# Vl822.net
KiCad netlist of a schematic drawn in Altium Designer
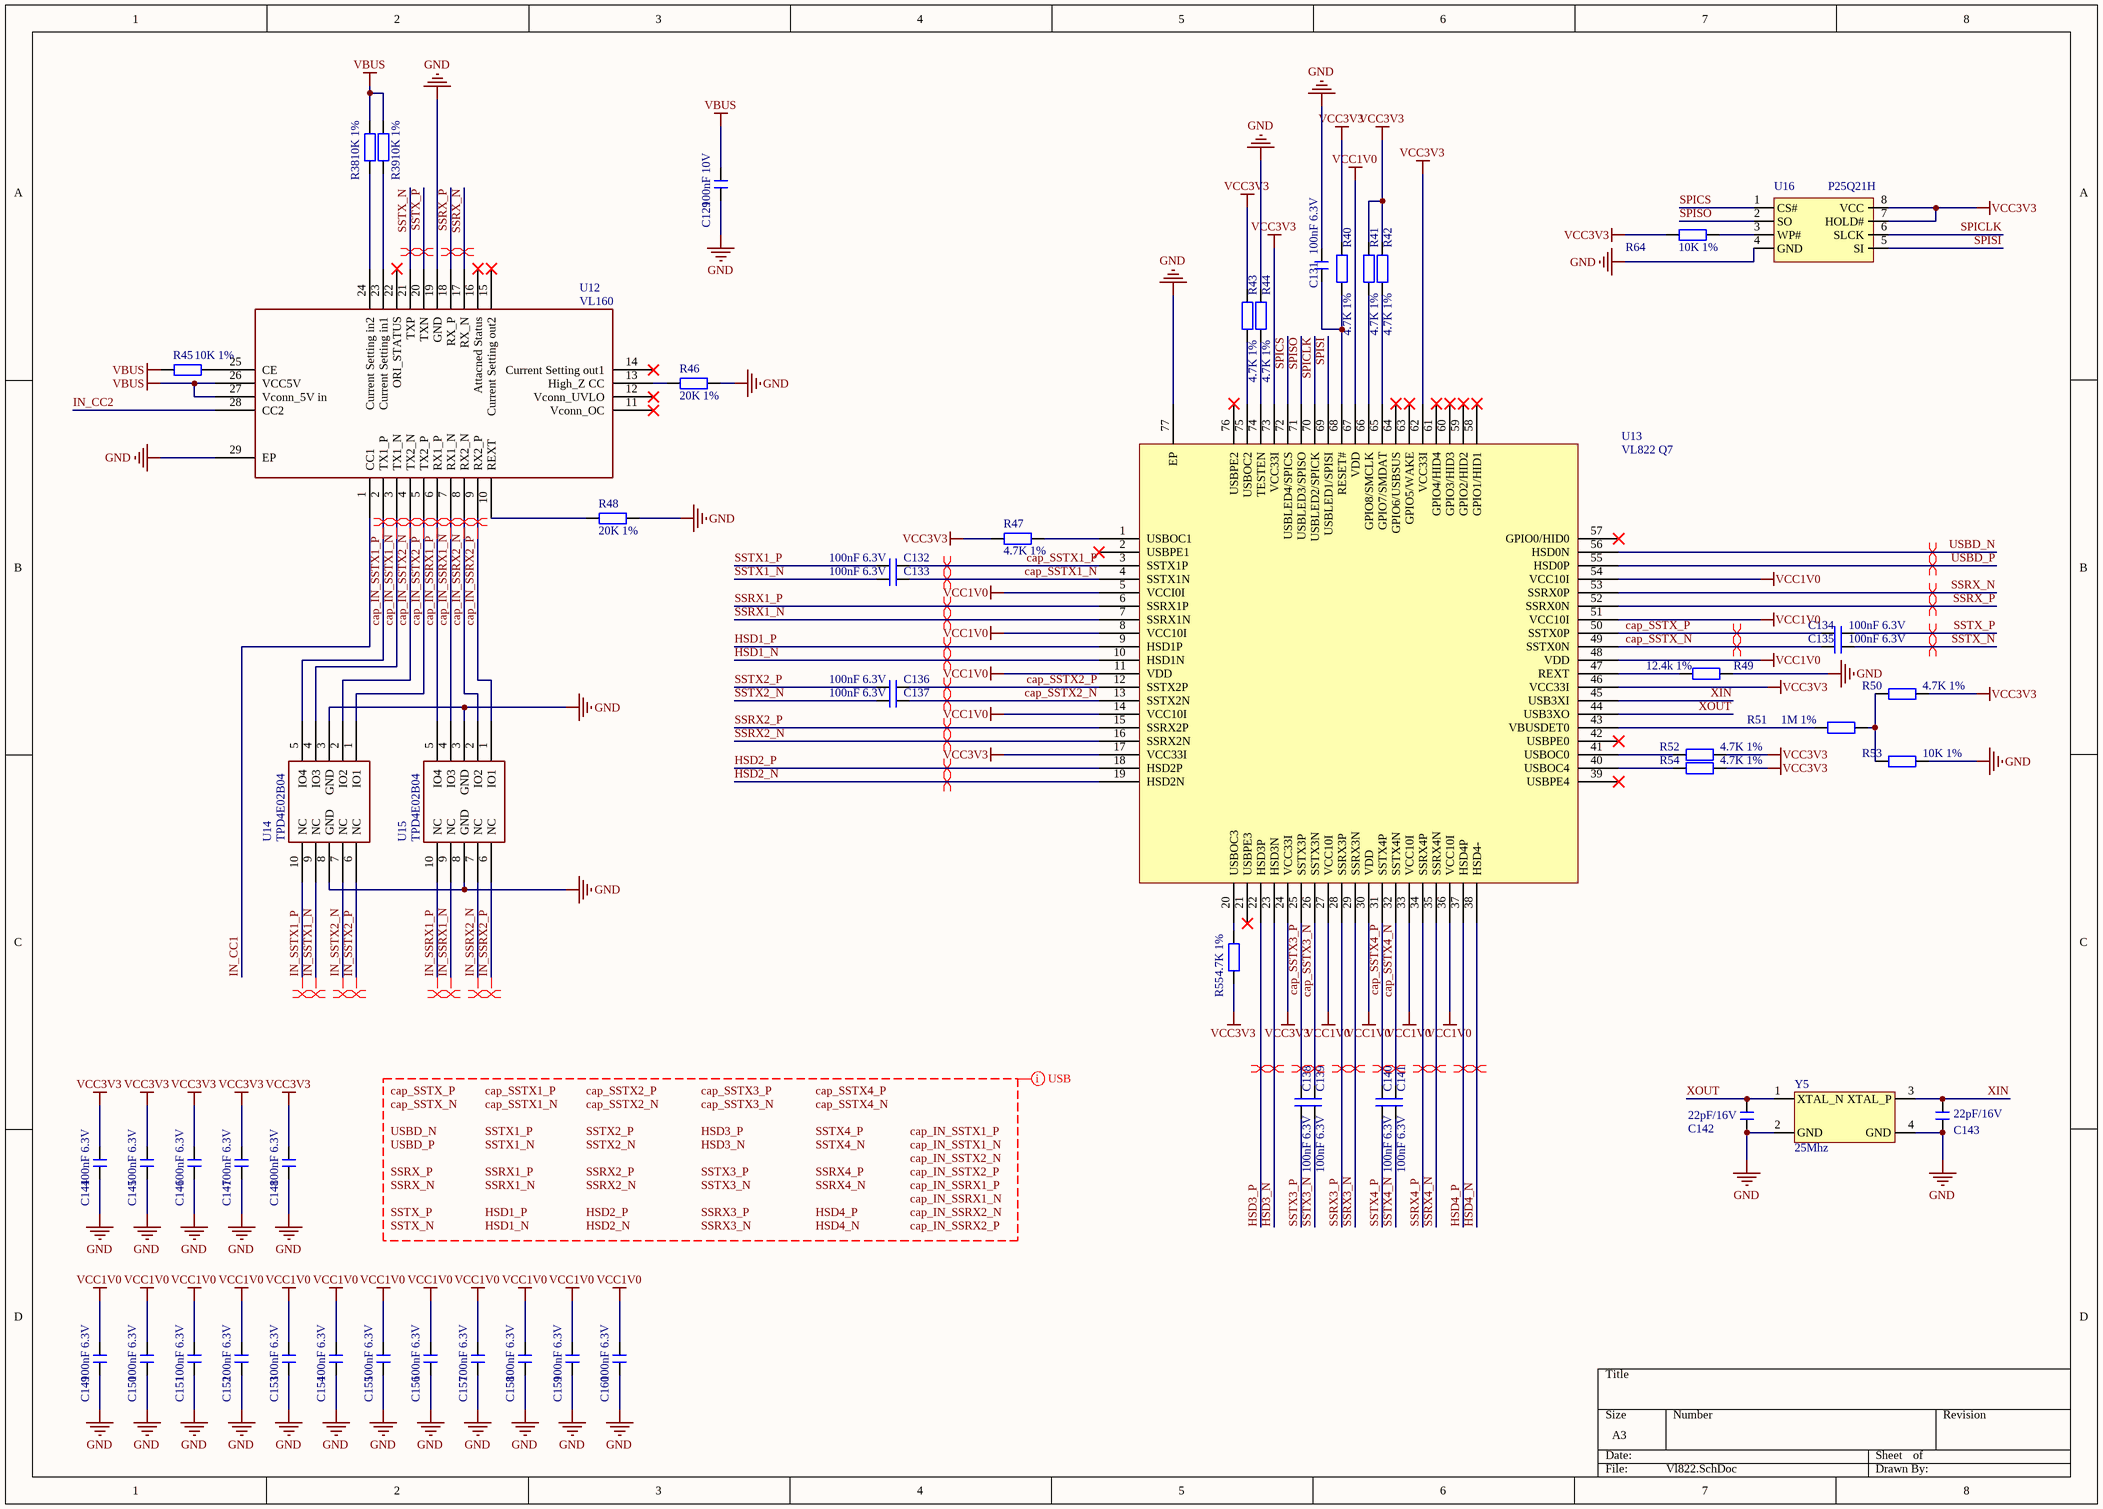
[diagram p0: Vl822.SchDoc]

(export (version "E")
  (design (tool "Eeschema 10.0.6"))
  (components
    (comp (ref "C129")
      (value "100nF 10V")
      (footprint "C0402_L")
      (description "无极性贴片电容")
      (fields (field (name "版权归属") "源创客"))
      (libsource (lib "Capacitor") (part "C"))
    )
    (comp (ref "C131")
      (value "100nF 6.3V")
      (footprint "C0402_L")
      (description "无极性贴片电容")
      (fields (field (name "版权归属") "源创客"))
      (libsource (lib "Capacitor") (part "C"))
    )
    (comp (ref "C132")
      (value "100nF 6.3V")
      (footprint "C0402_L")
      (description "无极性贴片电容")
      (fields (field (name "版权归属") "源创客"))
      (libsource (lib "Capacitor") (part "C"))
    )
    (comp (ref "C133")
      (value "100nF 6.3V")
      (footprint "C0402_L")
      (description "无极性贴片电容")
      (fields (field (name "版权归属") "源创客"))
      (libsource (lib "Capacitor") (part "C"))
    )
    (comp (ref "C134")
      (value "100nF 6.3V")
      (footprint "C0402_L")
      (description "无极性贴片电容")
      (fields (field (name "版权归属") "源创客"))
      (libsource (lib "Capacitor") (part "C"))
    )
    (comp (ref "C135")
      (value "100nF 6.3V")
      (footprint "C0402_L")
      (description "无极性贴片电容")
      (fields (field (name "版权归属") "源创客"))
      (libsource (lib "Capacitor") (part "C"))
    )
    (comp (ref "C136")
      (value "100nF 6.3V")
      (footprint "C0402_L")
      (description "无极性贴片电容")
      (fields (field (name "版权归属") "源创客"))
      (libsource (lib "Capacitor") (part "C"))
    )
    (comp (ref "C137")
      (value "100nF 6.3V")
      (footprint "C0402_L")
      (description "无极性贴片电容")
      (fields (field (name "版权归属") "源创客"))
      (libsource (lib "Capacitor") (part "C"))
    )
    (comp (ref "C138")
      (value "100nF 6.3V")
      (footprint "C0402_L")
      (description "无极性贴片电容")
      (fields (field (name "版权归属") "源创客"))
      (libsource (lib "Capacitor") (part "C"))
    )
    (comp (ref "C139")
      (value "100nF 6.3V")
      (footprint "C0402_L")
      (description "无极性贴片电容")
      (fields (field (name "版权归属") "源创客"))
      (libsource (lib "Capacitor") (part "C"))
    )
    (comp (ref "C140")
      (value "100nF 6.3V")
      (footprint "C0402_L")
      (description "无极性贴片电容")
      (fields (field (name "版权归属") "源创客"))
      (libsource (lib "Capacitor") (part "C"))
    )
    (comp (ref "C141")
      (value "100nF 6.3V")
      (footprint "C0402_L")
      (description "无极性贴片电容")
      (fields (field (name "版权归属") "源创客"))
      (libsource (lib "Capacitor") (part "C"))
    )
    (comp (ref "C142")
      (value "22pF/16V")
      (footprint "C0402_L")
      (description "无极性贴片电容")
      (fields (field (name "版权归属") "源创客"))
      (libsource (lib "Capacitor") (part "C"))
    )
    (comp (ref "C143")
      (value "22pF/16V")
      (footprint "C0402_L")
      (description "无极性贴片电容")
      (fields (field (name "版权归属") "源创客"))
      (libsource (lib "Capacitor") (part "C"))
    )
    (comp (ref "C144")
      (value "100nF 6.3V")
      (footprint "C0402_L")
      (description "无极性贴片电容")
      (fields (field (name "版权归属") "源创客"))
      (libsource (lib "Capacitor") (part "C"))
    )
    (comp (ref "C145")
      (value "100nF 6.3V")
      (footprint "C0402_L")
      (description "无极性贴片电容")
      (fields (field (name "版权归属") "源创客"))
      (libsource (lib "Capacitor") (part "C"))
    )
    (comp (ref "C146")
      (value "100nF 6.3V")
      (footprint "C0402_L")
      (description "无极性贴片电容")
      (fields (field (name "版权归属") "源创客"))
      (libsource (lib "Capacitor") (part "C"))
    )
    (comp (ref "C147")
      (value "100nF 6.3V")
      (footprint "C0402_L")
      (description "无极性贴片电容")
      (fields (field (name "版权归属") "源创客"))
      (libsource (lib "Capacitor") (part "C"))
    )
    (comp (ref "C148")
      (value "100nF 6.3V")
      (footprint "C0402_L")
      (description "无极性贴片电容")
      (fields (field (name "版权归属") "源创客"))
      (libsource (lib "Capacitor") (part "C"))
    )
    (comp (ref "C149")
      (value "100nF 6.3V")
      (footprint "C0402_L")
      (description "无极性贴片电容")
      (fields (field (name "版权归属") "源创客"))
      (libsource (lib "Capacitor") (part "C"))
    )
    (comp (ref "C150")
      (value "100nF 6.3V")
      (footprint "C0402_L")
      (description "无极性贴片电容")
      (fields (field (name "版权归属") "源创客"))
      (libsource (lib "Capacitor") (part "C"))
    )
    (comp (ref "C151")
      (value "100nF 6.3V")
      (footprint "C0402_L")
      (description "无极性贴片电容")
      (fields (field (name "版权归属") "源创客"))
      (libsource (lib "Capacitor") (part "C"))
    )
    (comp (ref "C152")
      (value "100nF 6.3V")
      (footprint "C0402_L")
      (description "无极性贴片电容")
      (fields (field (name "版权归属") "源创客"))
      (libsource (lib "Capacitor") (part "C"))
    )
    (comp (ref "C153")
      (value "100nF 6.3V")
      (footprint "C0402_L")
      (description "无极性贴片电容")
      (fields (field (name "版权归属") "源创客"))
      (libsource (lib "Capacitor") (part "C"))
    )
    (comp (ref "C154")
      (value "100nF 6.3V")
      (footprint "C0402_L")
      (description "无极性贴片电容")
      (fields (field (name "版权归属") "源创客"))
      (libsource (lib "Capacitor") (part "C"))
    )
    (comp (ref "C155")
      (value "100nF 6.3V")
      (footprint "C0402_L")
      (description "无极性贴片电容")
      (fields (field (name "版权归属") "源创客"))
      (libsource (lib "Capacitor") (part "C"))
    )
    (comp (ref "C156")
      (value "100nF 6.3V")
      (footprint "C0402_L")
      (description "无极性贴片电容")
      (fields (field (name "版权归属") "源创客"))
      (libsource (lib "Capacitor") (part "C"))
    )
    (comp (ref "C157")
      (value "100nF 6.3V")
      (footprint "C0402_L")
      (description "无极性贴片电容")
      (fields (field (name "版权归属") "源创客"))
      (libsource (lib "Capacitor") (part "C"))
    )
    (comp (ref "C158")
      (value "100nF 6.3V")
      (footprint "C0402_L")
      (description "无极性贴片电容")
      (fields (field (name "版权归属") "源创客"))
      (libsource (lib "Capacitor") (part "C"))
    )
    (comp (ref "C159")
      (value "100nF 6.3V")
      (footprint "C0402_L")
      (description "无极性贴片电容")
      (fields (field (name "版权归属") "源创客"))
      (libsource (lib "Capacitor") (part "C"))
    )
    (comp (ref "C160")
      (value "100nF 6.3V")
      (footprint "C0402_L")
      (description "无极性贴片电容")
      (fields (field (name "版权归属") "源创客"))
      (libsource (lib "Capacitor") (part "C"))
    )
    (comp (ref "R38")
      (value "10K 1%")
      (footprint "R0402_L")
      (description "贴片电阻")
      (fields (field (name "版权归属") "源创客"))
      (libsource (lib "Resistor") (part "R"))
    )
    (comp (ref "R39")
      (value "10K 1%")
      (footprint "R0402_L")
      (description "贴片电阻")
      (fields (field (name "版权归属") "源创客"))
      (libsource (lib "Resistor") (part "R"))
    )
    (comp (ref "R40")
      (value "4.7K 1%")
      (footprint "R0402_L")
      (description "贴片电阻")
      (fields (field (name "版权归属") "源创客"))
      (libsource (lib "Resistor") (part "R"))
    )
    (comp (ref "R41")
      (value "4.7K 1%")
      (footprint "R0402_L")
      (description "贴片电阻")
      (fields (field (name "版权归属") "源创客"))
      (libsource (lib "Resistor") (part "R"))
    )
    (comp (ref "R42")
      (value "4.7K 1%")
      (footprint "R0402_L")
      (description "贴片电阻")
      (fields (field (name "版权归属") "源创客"))
      (libsource (lib "Resistor") (part "R"))
    )
    (comp (ref "R43")
      (value "4.7K 1%")
      (footprint "R0402_L")
      (description "贴片电阻")
      (fields (field (name "版权归属") "源创客"))
      (libsource (lib "Resistor") (part "R"))
    )
    (comp (ref "R44")
      (value "4.7K 1%")
      (footprint "R0402_L")
      (description "贴片电阻")
      (fields (field (name "版权归属") "源创客"))
      (libsource (lib "Resistor") (part "R"))
    )
    (comp (ref "R45")
      (value "10K 1%")
      (footprint "R0402_L")
      (description "贴片电阻")
      (fields (field (name "版权归属") "源创客"))
      (libsource (lib "Resistor") (part "R"))
    )
    (comp (ref "R46")
      (value "20K 1%")
      (footprint "R0402_L")
      (description "贴片电阻")
      (fields (field (name "版权归属") "源创客"))
      (libsource (lib "Resistor") (part "R"))
    )
    (comp (ref "R47")
      (value "4.7K 1%")
      (footprint "R0402_L")
      (description "贴片电阻")
      (fields (field (name "版权归属") "源创客"))
      (libsource (lib "Resistor") (part "R"))
    )
    (comp (ref "R48")
      (value "20K 1%")
      (footprint "R0402_L")
      (description "贴片电阻")
      (fields (field (name "版权归属") "源创客"))
      (libsource (lib "Resistor") (part "R"))
    )
    (comp (ref "R49")
      (value "12.4k 1%")
      (footprint "R0402_L")
      (description "贴片电阻")
      (fields (field (name "版权归属") "源创客"))
      (libsource (lib "Resistor") (part "R"))
    )
    (comp (ref "R50")
      (value "4.7K 1%")
      (footprint "R0402_L")
      (description "贴片电阻")
      (fields (field (name "版权归属") "源创客"))
      (libsource (lib "Resistor") (part "R"))
    )
    (comp (ref "R51")
      (value "1M 1%")
      (footprint "R0402_L")
      (description "贴片电阻")
      (fields (field (name "版权归属") "源创客"))
      (libsource (lib "Resistor") (part "R"))
    )
    (comp (ref "R52")
      (value "4.7K 1%")
      (footprint "R0402_L")
      (description "贴片电阻")
      (fields (field (name "版权归属") "源创客"))
      (libsource (lib "Resistor") (part "R"))
    )
    (comp (ref "R53")
      (value "10K 1%")
      (footprint "R0402_L")
      (description "贴片电阻")
      (fields (field (name "版权归属") "源创客"))
      (libsource (lib "Resistor") (part "R"))
    )
    (comp (ref "R54")
      (value "4.7K 1%")
      (footprint "R0402_L")
      (description "贴片电阻")
      (fields (field (name "版权归属") "源创客"))
      (libsource (lib "Resistor") (part "R"))
    )
    (comp (ref "R55")
      (value "4.7K 1%")
      (footprint "R0402_L")
      (description "贴片电阻")
      (fields (field (name "版权归属") "源创客"))
      (libsource (lib "Resistor") (part "R"))
    )
    (comp (ref "R64")
      (value "10K 1%")
      (footprint "R0402_L")
      (description "贴片电阻")
      (fields (field (name "版权归属") "源创客"))
      (libsource (lib "Resistor") (part "R"))
    )
    (comp (ref "U12")
      (value "VL160")
      (footprint "MQFN-28_L4.5-W3.5-P0.40-BL-EP")
      (libsource (lib "Brage") (part "VL160"))
    )
    (comp (ref "U13")
      (value "VL822 Q7")
      (footprint "QFN-76_L9.0-W9.0-P0.40-EP6.3-TL")
      (libsource (lib "Brage") (part "VL822 Q7"))
    )
    (comp (ref "U14")
      (value "TPD4E02B04")
      (footprint "DIO_TPD4E02B04DQAR")
      (description "ESD")
      (libsource (lib "Diode") (part "TPD4E02B04"))
    )
    (comp (ref "U15")
      (value "TPD4E02B04")
      (footprint "DIO_TPD4E02B04DQAR")
      (description "ESD")
      (libsource (lib "Diode") (part "TPD4E02B04"))
    )
    (comp (ref "U16") (value "P25Q21H") (footprint "SOP8_L") (libsource (lib "Flash") (part "P25D40H")))
    (comp (ref "Y5") (value "25Mhz") (footprint "OSC 3225-4P") (libsource (lib "Crystal") (part "Crystal")))
  )
  (nets
    (net (code "1") (name "/HSD1_N") (class "Default")
      (node (ref "U13") (pin "10") (pinfunction "HSD1N_10") (pintype "passive"))
    )
    (net (code "2") (name "/HSD1_P") (class "Default")
      (node (ref "U13") (pin "9") (pinfunction "HSD1P_9") (pintype "passive"))
    )
    (net (code "3") (name "/HSD2_N") (class "Default")
      (node (ref "U13") (pin "19") (pinfunction "HSD2N_19") (pintype "passive"))
    )
    (net (code "4") (name "/HSD2_P") (class "Default")
      (node (ref "U13") (pin "18") (pinfunction "HSD2P_18") (pintype "passive"))
    )
    (net (code "5") (name "/HSD3_N") (class "Default")
      (node (ref "U13") (pin "23") (pinfunction "HSD3N_23") (pintype "passive"))
    )
    (net (code "6") (name "/HSD3_P") (class "Default")
      (node (ref "U13") (pin "22") (pinfunction "HSD3P_22") (pintype "passive"))
    )
    (net (code "7") (name "/HSD4_N") (class "Default")
      (node (ref "U13") (pin "38") (pinfunction "HSD4-_38") (pintype "passive"))
    )
    (net (code "8") (name "/HSD4_P") (class "Default")
      (node (ref "U13") (pin "37") (pinfunction "HSD4P_37") (pintype "passive"))
    )
    (net (code "9") (name "/IN_CC1") (class "Default")
      (node (ref "U12") (pin "1") (pinfunction "CC1_1") (pintype "passive"))
    )
    (net (code "10") (name "/IN_CC2") (class "Default")
      (node (ref "U12") (pin "28") (pinfunction "CC2_28") (pintype "passive"))
    )
    (net (code "11") (name "/IN_SSRX1_N") (class "Default")
      (node (ref "U15") (pin "9") (pinfunction "NC_9") (pintype "passive"))
    )
    (net (code "12") (name "/IN_SSRX1_P") (class "Default")
      (node (ref "U15") (pin "10") (pinfunction "NC_10") (pintype "passive"))
    )
    (net (code "13") (name "/IN_SSRX2_N") (class "Default")
      (node (ref "U15") (pin "7") (pinfunction "NC_7") (pintype "passive"))
    )
    (net (code "14") (name "/IN_SSRX2_P") (class "Default")
      (node (ref "U15") (pin "6") (pinfunction "NC_6") (pintype "passive"))
    )
    (net (code "15") (name "/IN_SSTX1_N") (class "Default")
      (node (ref "U14") (pin "9") (pinfunction "NC_9") (pintype "passive"))
    )
    (net (code "16") (name "/IN_SSTX1_P") (class "Default")
      (node (ref "U14") (pin "10") (pinfunction "NC_10") (pintype "passive"))
    )
    (net (code "17") (name "/IN_SSTX2_N") (class "Default")
      (node (ref "U14") (pin "7") (pinfunction "NC_7") (pintype "passive"))
    )
    (net (code "18") (name "/IN_SSTX2_P") (class "Default")
      (node (ref "U14") (pin "6") (pinfunction "NC_6") (pintype "passive"))
    )
    (net (code "19") (name "/SPICLK") (class "Default")
      (node (ref "U13") (pin "70") (pinfunction "USBLED2/SPICK_70") (pintype "passive"))
      (node (ref "U16") (pin "6") (pinfunction "SLCK_6") (pintype "passive"))
    )
    (net (code "20") (name "/SPICS") (class "Default")
      (node (ref "U13") (pin "72") (pinfunction "USBLED4/SPICS_72") (pintype "passive"))
      (node (ref "U16") (pin "1") (pinfunction "CS#_1") (pintype "passive"))
    )
    (net (code "21") (name "/SPISI") (class "Default")
      (node (ref "U13") (pin "69") (pinfunction "USBLED1/SPISI_69") (pintype "passive"))
      (node (ref "U16") (pin "5") (pinfunction "SI_5") (pintype "passive"))
    )
    (net (code "22") (name "/SPISO") (class "Default")
      (node (ref "U13") (pin "71") (pinfunction "USBLED3/SPISO_71") (pintype "passive"))
      (node (ref "U16") (pin "2") (pinfunction "SO_2") (pintype "passive"))
    )
    (net (code "23") (name "/SSRX1_N") (class "Default")
      (node (ref "U13") (pin "7") (pinfunction "SSRX1N_7") (pintype "passive"))
    )
    (net (code "24") (name "/SSRX1_P") (class "Default")
      (node (ref "U13") (pin "6") (pinfunction "SSRX1P_6") (pintype "passive"))
    )
    (net (code "25") (name "/SSRX2_N") (class "Default")
      (node (ref "U13") (pin "16") (pinfunction "SSRX2N_16") (pintype "passive"))
    )
    (net (code "26") (name "/SSRX2_P") (class "Default")
      (node (ref "U13") (pin "15") (pinfunction "SSRX2P_15") (pintype "passive"))
    )
    (net (code "27") (name "/SSRX3_N") (class "Default")
      (node (ref "U13") (pin "29") (pinfunction "SSRX3N_29") (pintype "passive"))
    )
    (net (code "28") (name "/SSRX3_P") (class "Default")
      (node (ref "U13") (pin "28") (pinfunction "SSRX3P_28") (pintype "passive"))
    )
    (net (code "29") (name "/SSRX4_N") (class "Default")
      (node (ref "U13") (pin "35") (pinfunction "SSRX4N_35") (pintype "passive"))
    )
    (net (code "30") (name "/SSRX4_P") (class "Default")
      (node (ref "U13") (pin "34") (pinfunction "SSRX4P_34") (pintype "passive"))
    )
    (net (code "31") (name "/SSRX_N") (class "Default")
      (node (ref "U12") (pin "17") (pinfunction "RX_N_17") (pintype "passive"))
      (node (ref "U13") (pin "53") (pinfunction "SSRX0P_53") (pintype "passive"))
    )
    (net (code "32") (name "/SSRX_P") (class "Default")
      (node (ref "U12") (pin "18") (pinfunction "RX_P_18") (pintype "passive"))
      (node (ref "U13") (pin "52") (pinfunction "SSRX0N_52") (pintype "passive"))
    )
    (net (code "33") (name "/SSTX1_N") (class "Default")
      (node (ref "C133") (pin "1") (pinfunction "1_1") (pintype "passive"))
    )
    (net (code "34") (name "/SSTX1_P") (class "Default")
      (node (ref "C132") (pin "1") (pinfunction "1_1") (pintype "passive"))
    )
    (net (code "35") (name "/SSTX2_N") (class "Default")
      (node (ref "C137") (pin "1") (pinfunction "1_1") (pintype "passive"))
    )
    (net (code "36") (name "/SSTX2_P") (class "Default")
      (node (ref "C136") (pin "1") (pinfunction "1_1") (pintype "passive"))
    )
    (net (code "37") (name "/SSTX3_N") (class "Default")
      (node (ref "C139") (pin "1") (pinfunction "1_1") (pintype "passive"))
    )
    (net (code "38") (name "/SSTX3_P") (class "Default")
      (node (ref "C138") (pin "1") (pinfunction "1_1") (pintype "passive"))
    )
    (net (code "39") (name "/SSTX4_N") (class "Default")
      (node (ref "C141") (pin "1") (pinfunction "1_1") (pintype "passive"))
    )
    (net (code "40") (name "/SSTX4_P") (class "Default")
      (node (ref "C140") (pin "1") (pinfunction "1_1") (pintype "passive"))
    )
    (net (code "41") (name "/SSTX_N") (class "Default")
      (node (ref "C135") (pin "1") (pinfunction "1_1") (pintype "passive"))
      (node (ref "U12") (pin "21") (pinfunction "TXP_21") (pintype "passive"))
    )
    (net (code "42") (name "/SSTX_P") (class "Default")
      (node (ref "C134") (pin "1") (pinfunction "1_1") (pintype "passive"))
      (node (ref "U12") (pin "20") (pinfunction "TXN_20") (pintype "passive"))
    )
    (net (code "43") (name "/USBD_N") (class "Default")
      (node (ref "U13") (pin "56") (pinfunction "HSD0N_56") (pintype "passive"))
    )
    (net (code "44") (name "/USBD_P") (class "Default")
      (node (ref "U13") (pin "55") (pinfunction "HSD0P_55") (pintype "passive"))
    )
    (net (code "45") (name "/XIN") (class "Default")
      (node (ref "C143") (pin "1") (pinfunction "1_1") (pintype "passive"))
      (node (ref "U13") (pin "45") (pinfunction "USB3XI_45") (pintype "passive"))
      (node (ref "Y5") (pin "3") (pinfunction "XTAL_P_3") (pintype "passive"))
    )
    (net (code "46") (name "/XOUT") (class "Default")
      (node (ref "C142") (pin "1") (pinfunction "1_1") (pintype "passive"))
      (node (ref "U13") (pin "44") (pinfunction "USB3XO_44") (pintype "passive"))
      (node (ref "Y5") (pin "1") (pinfunction "XTAL_N_1") (pintype "passive"))
    )
    (net (code "47") (name "/cap_IN_SSRX1_N") (class "Default")
      (node (ref "U12") (pin "7") (pinfunction "RX1_N_7") (pintype "passive"))
      (node (ref "U15") (pin "4") (pinfunction "IO3_4") (pintype "passive"))
    )
    (net (code "48") (name "/cap_IN_SSRX1_P") (class "Default")
      (node (ref "U12") (pin "6") (pinfunction "RX1_P_6") (pintype "passive"))
      (node (ref "U15") (pin "5") (pinfunction "IO4_5") (pintype "passive"))
    )
    (net (code "49") (name "/cap_IN_SSRX2_N") (class "Default")
      (node (ref "U12") (pin "8") (pinfunction "RX2_N_8") (pintype "passive"))
      (node (ref "U15") (pin "2") (pinfunction "IO2_2") (pintype "passive"))
    )
    (net (code "50") (name "/cap_IN_SSRX2_P") (class "Default")
      (node (ref "U12") (pin "9") (pinfunction "RX2_P_9") (pintype "passive"))
      (node (ref "U15") (pin "1") (pinfunction "IO1_1") (pintype "passive"))
    )
    (net (code "51") (name "/cap_IN_SSTX1_N") (class "Default")
      (node (ref "U12") (pin "3") (pinfunction "TX1_N_3") (pintype "passive"))
      (node (ref "U14") (pin "4") (pinfunction "IO3_4") (pintype "passive"))
    )
    (net (code "52") (name "/cap_IN_SSTX1_P") (class "Default")
      (node (ref "U12") (pin "2") (pinfunction "TX1_P_2") (pintype "passive"))
      (node (ref "U14") (pin "5") (pinfunction "IO4_5") (pintype "passive"))
    )
    (net (code "53") (name "/cap_IN_SSTX2_N") (class "Default")
      (node (ref "U12") (pin "4") (pinfunction "TX2_N_4") (pintype "passive"))
      (node (ref "U14") (pin "2") (pinfunction "IO2_2") (pintype "passive"))
    )
    (net (code "54") (name "/cap_IN_SSTX2_P") (class "Default")
      (node (ref "U12") (pin "5") (pinfunction "TX2_P_5") (pintype "passive"))
      (node (ref "U14") (pin "1") (pinfunction "IO1_1") (pintype "passive"))
    )
    (net (code "55") (name "/cap_SSTX1_N") (class "Default")
      (node (ref "C133") (pin "2") (pinfunction "2_2") (pintype "passive"))
      (node (ref "U13") (pin "4") (pinfunction "SSTX1N_4") (pintype "passive"))
    )
    (net (code "56") (name "/cap_SSTX1_P") (class "Default")
      (node (ref "C132") (pin "2") (pinfunction "2_2") (pintype "passive"))
      (node (ref "U13") (pin "3") (pinfunction "SSTX1P_3") (pintype "passive"))
    )
    (net (code "57") (name "/cap_SSTX2_N") (class "Default")
      (node (ref "C137") (pin "2") (pinfunction "2_2") (pintype "passive"))
      (node (ref "U13") (pin "13") (pinfunction "SSTX2N_13") (pintype "passive"))
    )
    (net (code "58") (name "/cap_SSTX2_P") (class "Default")
      (node (ref "C136") (pin "2") (pinfunction "2_2") (pintype "passive"))
      (node (ref "U13") (pin "12") (pinfunction "SSTX2P_12") (pintype "passive"))
    )
    (net (code "59") (name "/cap_SSTX3_N") (class "Default")
      (node (ref "C139") (pin "2") (pinfunction "2_2") (pintype "passive"))
      (node (ref "U13") (pin "26") (pinfunction "SSTX3N_26") (pintype "passive"))
    )
    (net (code "60") (name "/cap_SSTX3_P") (class "Default")
      (node (ref "C138") (pin "2") (pinfunction "2_2") (pintype "passive"))
      (node (ref "U13") (pin "25") (pinfunction "SSTX3P_25") (pintype "passive"))
    )
    (net (code "61") (name "/cap_SSTX4_N") (class "Default")
      (node (ref "C141") (pin "2") (pinfunction "2_2") (pintype "passive"))
      (node (ref "U13") (pin "32") (pinfunction "SSTX4N_32") (pintype "passive"))
    )
    (net (code "62") (name "/cap_SSTX4_P") (class "Default")
      (node (ref "C140") (pin "2") (pinfunction "2_2") (pintype "passive"))
      (node (ref "U13") (pin "31") (pinfunction "SSTX4P_31") (pintype "passive"))
    )
    (net (code "63") (name "/cap_SSTX_N") (class "Default")
      (node (ref "C135") (pin "2") (pinfunction "2_2") (pintype "passive"))
      (node (ref "U13") (pin "49") (pinfunction "SSTX0N_49") (pintype "passive"))
    )
    (net (code "64") (name "/cap_SSTX_P") (class "Default")
      (node (ref "C134") (pin "2") (pinfunction "2_2") (pintype "passive"))
      (node (ref "U13") (pin "50") (pinfunction "SSTX0P_50") (pintype "passive"))
    )
    (net (code "65") (name "GND") (class "Default")
      (node (ref "C129") (pin "1") (pinfunction "1_1") (pintype "passive"))
      (node (ref "C131") (pin "2") (pinfunction "2_2") (pintype "passive"))
      (node (ref "C142") (pin "2") (pinfunction "2_2") (pintype "passive"))
      (node (ref "C143") (pin "2") (pinfunction "2_2") (pintype "passive"))
      (node (ref "C144") (pin "1") (pinfunction "1_1") (pintype "passive"))
      (node (ref "C145") (pin "1") (pinfunction "1_1") (pintype "passive"))
      (node (ref "C146") (pin "1") (pinfunction "1_1") (pintype "passive"))
      (node (ref "C147") (pin "1") (pinfunction "1_1") (pintype "passive"))
      (node (ref "C148") (pin "1") (pinfunction "1_1") (pintype "passive"))
      (node (ref "C149") (pin "1") (pinfunction "1_1") (pintype "passive"))
      (node (ref "C150") (pin "1") (pinfunction "1_1") (pintype "passive"))
      (node (ref "C151") (pin "1") (pinfunction "1_1") (pintype "passive"))
      (node (ref "C152") (pin "1") (pinfunction "1_1") (pintype "passive"))
      (node (ref "C153") (pin "1") (pinfunction "1_1") (pintype "passive"))
      (node (ref "C154") (pin "1") (pinfunction "1_1") (pintype "passive"))
      (node (ref "C155") (pin "1") (pinfunction "1_1") (pintype "passive"))
      (node (ref "C156") (pin "1") (pinfunction "1_1") (pintype "passive"))
      (node (ref "C157") (pin "1") (pinfunction "1_1") (pintype "passive"))
      (node (ref "C158") (pin "1") (pinfunction "1_1") (pintype "passive"))
      (node (ref "C159") (pin "1") (pinfunction "1_1") (pintype "passive"))
      (node (ref "C160") (pin "1") (pinfunction "1_1") (pintype "passive"))
      (node (ref "R44") (pin "2") (pinfunction "2_2") (pintype "passive"))
      (node (ref "R46") (pin "1") (pinfunction "1_1") (pintype "passive"))
      (node (ref "R48") (pin "1") (pinfunction "1_1") (pintype "passive"))
      (node (ref "R49") (pin "2") (pinfunction "2_2") (pintype "passive"))
      (node (ref "R53") (pin "2") (pinfunction "2_2") (pintype "passive"))
      (node (ref "U12") (pin "19") (pinfunction "GND_19") (pintype "passive"))
      (node (ref "U12") (pin "29") (pinfunction "EP_29") (pintype "passive"))
      (node (ref "U13") (pin "77") (pinfunction "EP_77") (pintype "passive"))
      (node (ref "U14") (pin "3") (pinfunction "GND_3") (pintype "passive"))
      (node (ref "U14") (pin "8") (pinfunction "GND_8") (pintype "passive"))
      (node (ref "U15") (pin "3") (pinfunction "GND_3") (pintype "passive"))
      (node (ref "U15") (pin "8") (pinfunction "GND_8") (pintype "passive"))
      (node (ref "U16") (pin "4") (pinfunction "GND_4") (pintype "passive"))
      (node (ref "Y5") (pin "2") (pinfunction "GND_2") (pintype "passive"))
      (node (ref "Y5") (pin "4") (pinfunction "GND_4") (pintype "passive"))
    )
    (net (code "66") (name "Net-(R50-Pad1)") (class "Default")
      (node (ref "R50") (pin "1") (pinfunction "1_1") (pintype "passive"))
      (node (ref "R51") (pin "2") (pinfunction "2_2") (pintype "passive"))
      (node (ref "R53") (pin "1") (pinfunction "1_1") (pintype "passive"))
    )
    (net (code "67") (name "Net-(U12-CE)") (class "Default")
      (node (ref "R45") (pin "1") (pinfunction "1_1") (pintype "passive"))
      (node (ref "U12") (pin "25") (pinfunction "CE_25") (pintype "passive"))
    )
    (net (code "68") (name "Net-(U12-Current_Setting_in1)") (class "Default")
      (node (ref "R39") (pin "2") (pinfunction "2_2") (pintype "passive"))
      (node (ref "U12") (pin "23") (pinfunction "Current_Setting_in1_23") (pintype "passive"))
    )
    (net (code "69") (name "Net-(U12-Current_Setting_in2)") (class "Default")
      (node (ref "R38") (pin "2") (pinfunction "2_2") (pintype "passive"))
      (node (ref "U12") (pin "24") (pinfunction "Current_Setting_in2_24") (pintype "passive"))
    )
    (net (code "70") (name "Net-(U12-High_Z_CC)") (class "Default")
      (node (ref "R46") (pin "2") (pinfunction "2_2") (pintype "passive"))
      (node (ref "U12") (pin "13") (pinfunction "High_Z_CC_13") (pintype "passive"))
    )
    (net (code "71") (name "Net-(U12-REXT)") (class "Default")
      (node (ref "R48") (pin "2") (pinfunction "2_2") (pintype "passive"))
      (node (ref "U12") (pin "10") (pinfunction "REXT_10") (pintype "passive"))
    )
    (net (code "72") (name "Net-(U13-GPIO7{slash}SMDAT)") (class "Default")
      (node (ref "R42") (pin "1") (pinfunction "1_1") (pintype "passive"))
      (node (ref "U13") (pin "65") (pinfunction "GPIO7/SMDAT_65") (pintype "passive"))
    )
    (net (code "73") (name "Net-(U13-GPIO8{slash}SMCLK)") (class "Default")
      (node (ref "R41") (pin "1") (pinfunction "1_1") (pintype "passive"))
      (node (ref "U13") (pin "66") (pinfunction "GPIO8/SMCLK_66") (pintype "passive"))
    )
    (net (code "74") (name "Net-(U13-RESET#)") (class "Default")
      (node (ref "C131") (pin "1") (pinfunction "1_1") (pintype "passive"))
      (node (ref "R40") (pin "1") (pinfunction "1_1") (pintype "passive"))
      (node (ref "U13") (pin "68") (pinfunction "RESET#_68") (pintype "passive"))
    )
    (net (code "75") (name "Net-(U13-REXT)") (class "Default")
      (node (ref "R49") (pin "1") (pinfunction "1_1") (pintype "passive"))
      (node (ref "U13") (pin "47") (pinfunction "REXT_47") (pintype "passive"))
    )
    (net (code "76") (name "Net-(U13-TESTEN)") (class "Default")
      (node (ref "R44") (pin "1") (pinfunction "1_1") (pintype "passive"))
      (node (ref "U13") (pin "74") (pinfunction "TESTEN_74") (pintype "passive"))
    )
    (net (code "77") (name "Net-(U13-USBOC0)") (class "Default")
      (node (ref "R52") (pin "1") (pinfunction "1_1") (pintype "passive"))
      (node (ref "U13") (pin "41") (pinfunction "USBOC0_41") (pintype "passive"))
    )
    (net (code "78") (name "Net-(U13-USBOC1)") (class "Default")
      (node (ref "R47") (pin "1") (pinfunction "1_1") (pintype "passive"))
      (node (ref "U13") (pin "1") (pinfunction "USBOC1_1") (pintype "passive"))
    )
    (net (code "79") (name "Net-(U13-USBOC2)") (class "Default")
      (node (ref "R43") (pin "1") (pinfunction "1_1") (pintype "passive"))
      (node (ref "U13") (pin "75") (pinfunction "USBOC2_75") (pintype "passive"))
    )
    (net (code "80") (name "Net-(U13-USBOC3)") (class "Default")
      (node (ref "R55") (pin "1") (pinfunction "1_1") (pintype "passive"))
      (node (ref "U13") (pin "20") (pinfunction "USBOC3_20") (pintype "passive"))
    )
    (net (code "81") (name "Net-(U13-USBOC4)") (class "Default")
      (node (ref "R54") (pin "1") (pinfunction "1_1") (pintype "passive"))
      (node (ref "U13") (pin "40") (pinfunction "USBOC4_40") (pintype "passive"))
    )
    (net (code "82") (name "Net-(U13-VBUSDET0)") (class "Default")
      (node (ref "R51") (pin "1") (pinfunction "1_1") (pintype "passive"))
      (node (ref "U13") (pin "43") (pinfunction "VBUSDET0_43") (pintype "passive"))
    )
    (net (code "83") (name "Net-(U16-WP#)") (class "Default")
      (node (ref "R64") (pin "1") (pinfunction "1_1") (pintype "passive"))
      (node (ref "U16") (pin "3") (pinfunction "WP#_3") (pintype "passive"))
    )
    (net (code "84") (name "VBUS") (class "Default")
      (node (ref "C129") (pin "2") (pinfunction "2_2") (pintype "passive"))
      (node (ref "R38") (pin "1") (pinfunction "1_1") (pintype "passive"))
      (node (ref "R39") (pin "1") (pinfunction "1_1") (pintype "passive"))
      (node (ref "R45") (pin "2") (pinfunction "2_2") (pintype "passive"))
      (node (ref "U12") (pin "26") (pinfunction "VCC5V_26") (pintype "passive"))
      (node (ref "U12") (pin "27") (pinfunction "Vconn_5V_in_27") (pintype "passive"))
    )
    (net (code "85") (name "VCC1V0") (class "Default")
      (node (ref "C149") (pin "2") (pinfunction "2_2") (pintype "passive"))
      (node (ref "C150") (pin "2") (pinfunction "2_2") (pintype "passive"))
      (node (ref "C151") (pin "2") (pinfunction "2_2") (pintype "passive"))
      (node (ref "C152") (pin "2") (pinfunction "2_2") (pintype "passive"))
      (node (ref "C153") (pin "2") (pinfunction "2_2") (pintype "passive"))
      (node (ref "C154") (pin "2") (pinfunction "2_2") (pintype "passive"))
      (node (ref "C155") (pin "2") (pinfunction "2_2") (pintype "passive"))
      (node (ref "C156") (pin "2") (pinfunction "2_2") (pintype "passive"))
      (node (ref "C157") (pin "2") (pinfunction "2_2") (pintype "passive"))
      (node (ref "C158") (pin "2") (pinfunction "2_2") (pintype "passive"))
      (node (ref "C159") (pin "2") (pinfunction "2_2") (pintype "passive"))
      (node (ref "C160") (pin "2") (pinfunction "2_2") (pintype "passive"))
      (node (ref "U13") (pin "11") (pinfunction "VDD_11") (pintype "passive"))
      (node (ref "U13") (pin "14") (pinfunction "VCC10I_14") (pintype "passive"))
      (node (ref "U13") (pin "27") (pinfunction "VCC10I_27") (pintype "passive"))
      (node (ref "U13") (pin "30") (pinfunction "VDD_30") (pintype "passive"))
      (node (ref "U13") (pin "33") (pinfunction "VCC10I_33") (pintype "passive"))
      (node (ref "U13") (pin "36") (pinfunction "VCC10I_36") (pintype "passive"))
      (node (ref "U13") (pin "48") (pinfunction "VDD_48") (pintype "passive"))
      (node (ref "U13") (pin "5") (pinfunction "VCCI0I_5") (pintype "passive"))
      (node (ref "U13") (pin "51") (pinfunction "VCC10I_51") (pintype "passive"))
      (node (ref "U13") (pin "54") (pinfunction "VCC10I_54") (pintype "passive"))
      (node (ref "U13") (pin "67") (pinfunction "VDD_67") (pintype "passive"))
      (node (ref "U13") (pin "8") (pinfunction "VCC10I_8") (pintype "passive"))
    )
    (net (code "86") (name "VCC3V3") (class "Default")
      (node (ref "C144") (pin "2") (pinfunction "2_2") (pintype "passive"))
      (node (ref "C145") (pin "2") (pinfunction "2_2") (pintype "passive"))
      (node (ref "C146") (pin "2") (pinfunction "2_2") (pintype "passive"))
      (node (ref "C147") (pin "2") (pinfunction "2_2") (pintype "passive"))
      (node (ref "C148") (pin "2") (pinfunction "2_2") (pintype "passive"))
      (node (ref "R40") (pin "2") (pinfunction "2_2") (pintype "passive"))
      (node (ref "R41") (pin "2") (pinfunction "2_2") (pintype "passive"))
      (node (ref "R42") (pin "2") (pinfunction "2_2") (pintype "passive"))
      (node (ref "R43") (pin "2") (pinfunction "2_2") (pintype "passive"))
      (node (ref "R47") (pin "2") (pinfunction "2_2") (pintype "passive"))
      (node (ref "R50") (pin "2") (pinfunction "2_2") (pintype "passive"))
      (node (ref "R52") (pin "2") (pinfunction "2_2") (pintype "passive"))
      (node (ref "R54") (pin "2") (pinfunction "2_2") (pintype "passive"))
      (node (ref "R55") (pin "2") (pinfunction "2_2") (pintype "passive"))
      (node (ref "R64") (pin "2") (pinfunction "2_2") (pintype "passive"))
      (node (ref "U13") (pin "17") (pinfunction "VCC33I_17") (pintype "passive"))
      (node (ref "U13") (pin "24") (pinfunction "VCC33I_24") (pintype "passive"))
      (node (ref "U13") (pin "46") (pinfunction "VCC33I_46") (pintype "passive"))
      (node (ref "U13") (pin "62") (pinfunction "VCC33I_62") (pintype "passive"))
      (node (ref "U13") (pin "73") (pinfunction "VCC33I_73") (pintype "passive"))
      (node (ref "U16") (pin "7") (pinfunction "HOLD#_7") (pintype "passive"))
      (node (ref "U16") (pin "8") (pinfunction "VCC_8") (pintype "passive"))
    )
    (net (code "87") (name "unconnected-(U12-Attacned_Status-Pad16)") (class "Default")
      (node (ref "U12") (pin "16") (pinfunction "Attacned_Status_16") (pintype "passive+no_connect"))
    )
    (net (code "88") (name "unconnected-(U12-Current_Setting_out1-Pad14)") (class "Default")
      (node (ref "U12") (pin "14") (pinfunction "Current_Setting_out1_14") (pintype "passive+no_connect"))
    )
    (net (code "89") (name "unconnected-(U12-Current_Setting_out2-Pad15)") (class "Default")
      (node (ref "U12") (pin "15") (pinfunction "Current_Setting_out2_15") (pintype "passive+no_connect"))
    )
    (net (code "90") (name "unconnected-(U12-ORI_STATUS-Pad22)") (class "Default")
      (node (ref "U12") (pin "22") (pinfunction "ORI_STATUS_22") (pintype "passive+no_connect"))
    )
    (net (code "91") (name "unconnected-(U12-Vconn_OC-Pad11)") (class "Default")
      (node (ref "U12") (pin "11") (pinfunction "Vconn_OC_11") (pintype "passive+no_connect"))
    )
    (net (code "92") (name "unconnected-(U12-Vconn_UVLO-Pad12)") (class "Default")
      (node (ref "U12") (pin "12") (pinfunction "Vconn_UVLO_12") (pintype "passive+no_connect"))
    )
    (net (code "93") (name "unconnected-(U13-GPIO0{slash}HID0-Pad57)") (class "Default")
      (node (ref "U13") (pin "57") (pinfunction "GPIO0/HID0_57") (pintype "passive+no_connect"))
    )
    (net (code "94") (name "unconnected-(U13-GPIO1{slash}HID1-Pad58)") (class "Default")
      (node (ref "U13") (pin "58") (pinfunction "GPIO1/HID1_58") (pintype "passive+no_connect"))
    )
    (net (code "95") (name "unconnected-(U13-GPIO2{slash}HID2-Pad59)") (class "Default")
      (node (ref "U13") (pin "59") (pinfunction "GPIO2/HID2_59") (pintype "passive+no_connect"))
    )
    (net (code "96") (name "unconnected-(U13-GPIO3{slash}HID3-Pad60)") (class "Default")
      (node (ref "U13") (pin "60") (pinfunction "GPIO3/HID3_60") (pintype "passive+no_connect"))
    )
    (net (code "97") (name "unconnected-(U13-GPIO4{slash}HID4-Pad61)") (class "Default")
      (node (ref "U13") (pin "61") (pinfunction "GPIO4/HID4_61") (pintype "passive+no_connect"))
    )
    (net (code "98") (name "unconnected-(U13-GPIO5{slash}WAKE-Pad63)") (class "Default")
      (node (ref "U13") (pin "63") (pinfunction "GPIO5/WAKE_63") (pintype "passive+no_connect"))
    )
    (net (code "99") (name "unconnected-(U13-GPIO6{slash}USBSUS-Pad64)") (class "Default")
      (node (ref "U13") (pin "64") (pinfunction "GPIO6/USBSUS_64") (pintype "passive+no_connect"))
    )
    (net (code "100") (name "unconnected-(U13-USBPE0-Pad42)") (class "Default")
      (node (ref "U13") (pin "42") (pinfunction "USBPE0_42") (pintype "passive+no_connect"))
    )
    (net (code "101") (name "unconnected-(U13-USBPE1-Pad2)") (class "Default")
      (node (ref "U13") (pin "2") (pinfunction "USBPE1_2") (pintype "passive+no_connect"))
    )
    (net (code "102") (name "unconnected-(U13-USBPE2-Pad76)") (class "Default")
      (node (ref "U13") (pin "76") (pinfunction "USBPE2_76") (pintype "passive+no_connect"))
    )
    (net (code "103") (name "unconnected-(U13-USBPE3-Pad21)") (class "Default")
      (node (ref "U13") (pin "21") (pinfunction "USBPE3_21") (pintype "passive+no_connect"))
    )
    (net (code "104") (name "unconnected-(U13-USBPE4-Pad39)") (class "Default")
      (node (ref "U13") (pin "39") (pinfunction "USBPE4_39") (pintype "passive+no_connect"))
    )
  )
)
